# ERN_MainPowerV2.net
KiCad netlist of a schematic drawn in Altium Designer
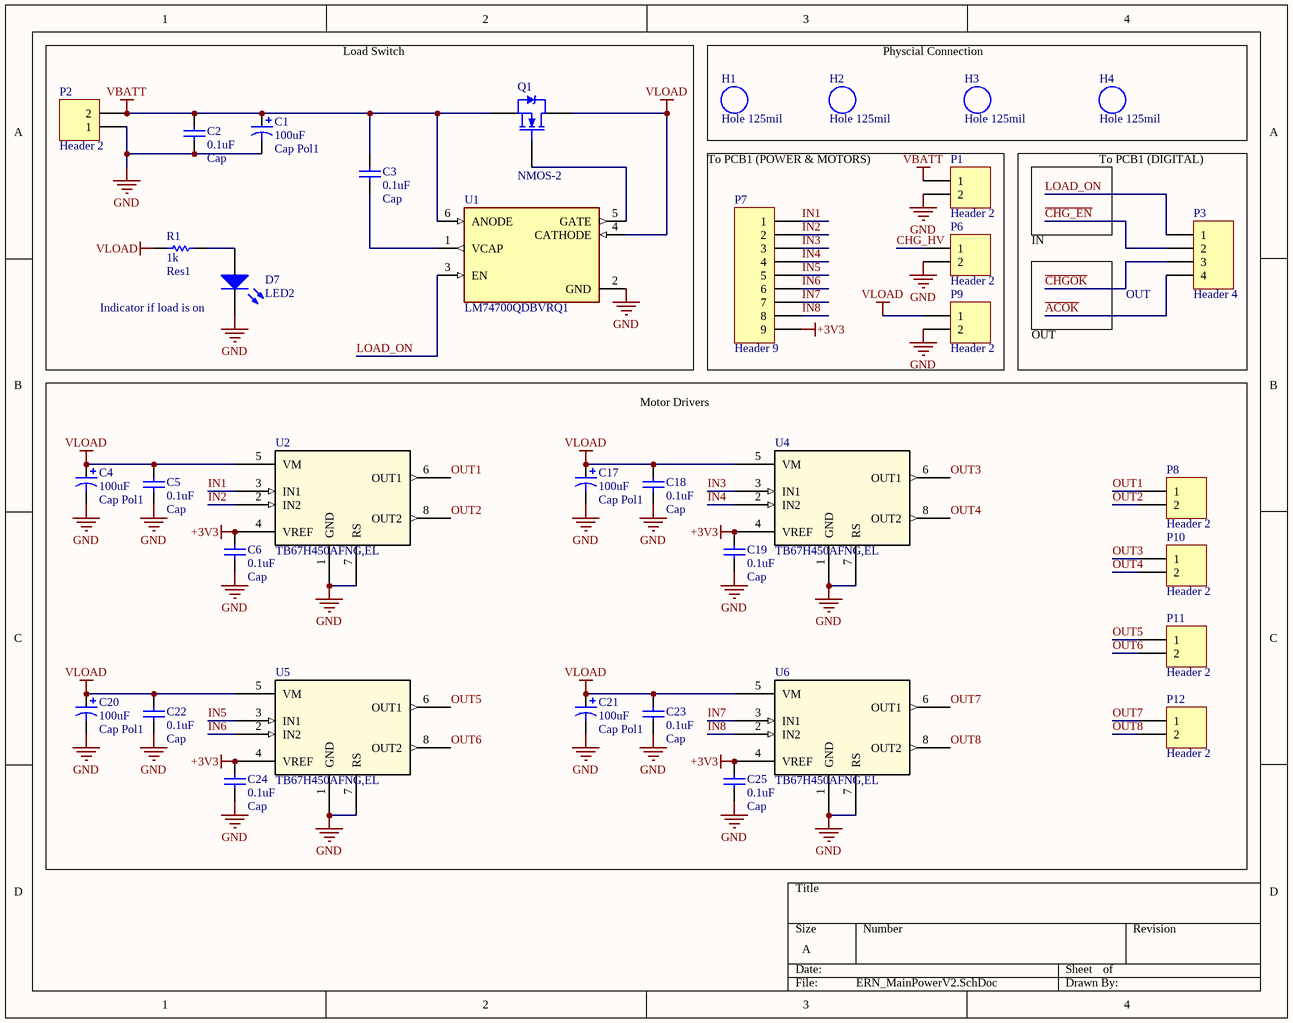
[diagram p0: ERN_MainPowerV2.SchDoc]

(export (version "E")
  (design (tool "Eeschema 10.0.6"))
  (components
    (comp (ref "C1")
      (value "Cap Pol1")
      (footprint "Cap_47uF_100uF")
      (description "Polarized Capacitor (Radial)")
      (fields (field (name "ALTIUM_VALUE") "100uF") (field (name "PUBLISHER") "Altium Limited"))
      (libsource (lib "Miscellaneous Devices") (part "Cap Pol1"))
    )
    (comp (ref "C2")
      (value "Cap")
      (footprint "RAD-0.3")
      (description "Capacitor")
      (fields (field (name "ALTIUM_VALUE") "0.1uF") (field (name "PUBLISHER") "Altium Limited"))
      (libsource (lib "Miscellaneous Devices") (part "Cap"))
    )
    (comp (ref "C3")
      (value "Cap")
      (footprint "C0805")
      (description "Capacitor")
      (fields (field (name "ALTIUM_VALUE") "0.1uF") (field (name "PUBLISHER") "Altium Limited"))
      (libsource (lib "Miscellaneous Devices") (part "Cap"))
    )
    (comp (ref "C4")
      (value "Cap Pol1")
      (footprint "Cap_47uF_100uF")
      (description "Polarized Capacitor (Radial)")
      (fields (field (name "ALTIUM_VALUE") "100uF") (field (name "PUBLISHER") "Altium Limited"))
      (libsource (lib "Miscellaneous Devices") (part "Cap Pol1"))
    )
    (comp (ref "C5")
      (value "Cap")
      (footprint "C0805")
      (description "Capacitor")
      (fields (field (name "ALTIUM_VALUE") "0.1uF") (field (name "PUBLISHER") "Altium Limited"))
      (libsource (lib "Miscellaneous Devices") (part "Cap"))
    )
    (comp (ref "C6")
      (value "Cap")
      (footprint "RAD-0.3")
      (description "Capacitor")
      (fields (field (name "ALTIUM_VALUE") "0.1uF") (field (name "PUBLISHER") "Altium Limited"))
      (libsource (lib "Miscellaneous Devices") (part "Cap"))
    )
    (comp (ref "C17")
      (value "Cap Pol1")
      (footprint "Cap_47uF_100uF")
      (description "Polarized Capacitor (Radial)")
      (fields (field (name "ALTIUM_VALUE") "100uF") (field (name "PUBLISHER") "Altium Limited"))
      (libsource (lib "Miscellaneous Devices") (part "Cap Pol1"))
    )
    (comp (ref "C18")
      (value "Cap")
      (footprint "C0805")
      (description "Capacitor")
      (fields (field (name "ALTIUM_VALUE") "0.1uF") (field (name "PUBLISHER") "Altium Limited"))
      (libsource (lib "Miscellaneous Devices") (part "Cap"))
    )
    (comp (ref "C19")
      (value "Cap")
      (footprint "RAD-0.3")
      (description "Capacitor")
      (fields (field (name "ALTIUM_VALUE") "0.1uF") (field (name "PUBLISHER") "Altium Limited"))
      (libsource (lib "Miscellaneous Devices") (part "Cap"))
    )
    (comp (ref "C20")
      (value "Cap Pol1")
      (footprint "Cap_47uF_100uF")
      (description "Polarized Capacitor (Radial)")
      (fields (field (name "ALTIUM_VALUE") "100uF") (field (name "PUBLISHER") "Altium Limited"))
      (libsource (lib "Miscellaneous Devices") (part "Cap Pol1"))
    )
    (comp (ref "C21")
      (value "Cap Pol1")
      (footprint "Cap_47uF_100uF")
      (description "Polarized Capacitor (Radial)")
      (fields (field (name "ALTIUM_VALUE") "100uF") (field (name "PUBLISHER") "Altium Limited"))
      (libsource (lib "Miscellaneous Devices") (part "Cap Pol1"))
    )
    (comp (ref "C22")
      (value "Cap")
      (footprint "C0805")
      (description "Capacitor")
      (fields (field (name "ALTIUM_VALUE") "0.1uF") (field (name "PUBLISHER") "Altium Limited"))
      (libsource (lib "Miscellaneous Devices") (part "Cap"))
    )
    (comp (ref "C23")
      (value "Cap")
      (footprint "C0805")
      (description "Capacitor")
      (fields (field (name "ALTIUM_VALUE") "0.1uF") (field (name "PUBLISHER") "Altium Limited"))
      (libsource (lib "Miscellaneous Devices") (part "Cap"))
    )
    (comp (ref "C24")
      (value "Cap")
      (footprint "RAD-0.3")
      (description "Capacitor")
      (fields (field (name "ALTIUM_VALUE") "0.1uF") (field (name "PUBLISHER") "Altium Limited"))
      (libsource (lib "Miscellaneous Devices") (part "Cap"))
    )
    (comp (ref "C25")
      (value "Cap")
      (footprint "RAD-0.3")
      (description "Capacitor")
      (fields (field (name "ALTIUM_VALUE") "0.1uF") (field (name "PUBLISHER") "Altium Limited"))
      (libsource (lib "Miscellaneous Devices") (part "Cap"))
    )
    (comp (ref "D7")
      (value "LED2")
      (footprint "led-0")
      (description "Typical RED, GREEN, YELLOW, AMBER GaAs LED")
      (fields (field (name "PUBLISHER") "Altium Limited"))
      (libsource (lib "Miscellaneous Devices") (part "LED2"))
    )
    (comp (ref "H1")
      (value "Hole 125mil")
      (footprint "Hole 125mil")
      (libsource (lib "ECE Lib 22") (part "Hole 125mil"))
    )
    (comp (ref "H2")
      (value "Hole 125mil")
      (footprint "Hole 125mil")
      (libsource (lib "ECE Lib 22") (part "Hole 125mil"))
    )
    (comp (ref "H3")
      (value "Hole 125mil")
      (footprint "Hole 125mil")
      (libsource (lib "ECE Lib 22") (part "Hole 125mil"))
    )
    (comp (ref "H4")
      (value "Hole 125mil")
      (footprint "Hole 125mil")
      (libsource (lib "ECE Lib 22") (part "Hole 125mil"))
    )
    (comp (ref "P1")
      (value "Header 2")
      (footprint "HDR1X2")
      (description "Header, 2-Pin")
      (fields (field (name "PUBLISHER") "Altium Limited"))
      (libsource (lib "Miscellaneous Connectors") (part "Header 2"))
    )
    (comp (ref "P2")
      (value "Header 2")
      (footprint "HDR1X2")
      (description "Header, 2-Pin")
      (fields (field (name "PUBLISHER") "Altium Limited"))
      (libsource (lib "") (part "Header 2_1"))
    )
    (comp (ref "P3")
      (value "Header 4")
      (footprint "HDR1X4")
      (description "Header, 4-Pin")
      (fields (field (name "PUBLISHER") "Altium Limited"))
      (libsource (lib "Miscellaneous Connectors") (part "Header 4"))
    )
    (comp (ref "P6")
      (value "Header 2")
      (footprint "HDR1X2")
      (description "Header, 2-Pin")
      (fields (field (name "PUBLISHER") "Altium Limited"))
      (libsource (lib "Miscellaneous Connectors") (part "Header 2"))
    )
    (comp (ref "P7")
      (value "Header 9")
      (footprint "HDR1X9")
      (description "Header, 9-Pin")
      (fields (field (name "PUBLISHER") "Altium Limited"))
      (libsource (lib "Miscellaneous Connectors") (part "Header 9"))
    )
    (comp (ref "P8")
      (value "Header 2")
      (footprint "HDR1X2")
      (description "Header, 2-Pin")
      (fields (field (name "PUBLISHER") "Altium Limited"))
      (libsource (lib "Miscellaneous Connectors") (part "Header 2"))
    )
    (comp (ref "P9")
      (value "Header 2")
      (footprint "HDR1X2")
      (description "Header, 2-Pin")
      (fields (field (name "PUBLISHER") "Altium Limited"))
      (libsource (lib "Miscellaneous Connectors") (part "Header 2"))
    )
    (comp (ref "P10")
      (value "Header 2")
      (footprint "HDR1X2")
      (description "Header, 2-Pin")
      (fields (field (name "PUBLISHER") "Altium Limited"))
      (libsource (lib "Miscellaneous Connectors") (part "Header 2"))
    )
    (comp (ref "P11")
      (value "Header 2")
      (footprint "HDR1X2")
      (description "Header, 2-Pin")
      (fields (field (name "PUBLISHER") "Altium Limited"))
      (libsource (lib "Miscellaneous Connectors") (part "Header 2"))
    )
    (comp (ref "P12")
      (value "Header 2")
      (footprint "HDR1X2")
      (description "Header, 2-Pin")
      (fields (field (name "PUBLISHER") "Altium Limited"))
      (libsource (lib "Miscellaneous Connectors") (part "Header 2"))
    )
    (comp (ref "Q1")
      (value "NMOS-2")
      (footprint "TO-220AB")
      (description "N-Channel Power MOSFET")
      (fields (field (name "PUBLISHER") "Altium Limited"))
      (libsource (lib "Miscellaneous Devices") (part "NMOS-2"))
    )
    (comp (ref "R1")
      (value "Res1")
      (footprint "AXIAL-0.3")
      (description "Resistor")
      (fields (field (name "ALTIUM_VALUE") "1k") (field (name "PUBLISHER") "Altium Limited"))
      (libsource (lib "Miscellaneous Devices") (part "Res1"))
    )
    (comp (ref "U1")
      (value "LM74700QDBVRQ1")
      (footprint "SOT95P280X145-6N")
      (description "3.2-V to 65-V, 80-uA IQ automotive ideal diode controller")
      (fields (field (name "MF") "Texas Instruments"))
      (libsource (lib "ERN") (part "LM74700QDBVRQ1"))
    )
    (comp (ref "U2")
      (value "TB67H450AFNG,EL")
      (footprint "P-HSOP8-0405-1.27-002_TOS")
      (description "Toshiba Motor Driver IC")
      (fields (field (name "COPYRIGHT") "Copyright (C) 2025 Ultra Librarian. All rights reserved."))
      (libsource (lib "ERN") (part "TB67H450AFNG,EL"))
    )
    (comp (ref "U4")
      (value "TB67H450AFNG,EL")
      (footprint "P-HSOP8-0405-1.27-002_TOS")
      (description "Toshiba Motor Driver IC")
      (fields (field (name "COPYRIGHT") "Copyright (C) 2025 Ultra Librarian. All rights reserved."))
      (libsource (lib "ERN") (part "TB67H450AFNG,EL"))
    )
    (comp (ref "U5")
      (value "TB67H450AFNG,EL")
      (footprint "P-HSOP8-0405-1.27-002_TOS")
      (description "Toshiba Motor Driver IC")
      (fields (field (name "COPYRIGHT") "Copyright (C) 2025 Ultra Librarian. All rights reserved."))
      (libsource (lib "ERN") (part "TB67H450AFNG,EL"))
    )
    (comp (ref "U6")
      (value "TB67H450AFNG,EL")
      (footprint "P-HSOP8-0405-1.27-002_TOS")
      (description "Toshiba Motor Driver IC")
      (fields (field (name "COPYRIGHT") "Copyright (C) 2025 Ultra Librarian. All rights reserved."))
      (libsource (lib "ERN") (part "TB67H450AFNG,EL"))
    )
  )
  (nets
    (net (code "1") (name "+3V3") (class "Default")
      (node (ref "C19") (pin "2") (pinfunction "2_2") (pintype "passive"))
      (node (ref "C24") (pin "2") (pinfunction "2_2") (pintype "passive"))
      (node (ref "C25") (pin "2") (pinfunction "2_2") (pintype "passive"))
      (node (ref "C6") (pin "2") (pinfunction "2_2") (pintype "passive"))
      (node (ref "P7") (pin "9") (pinfunction "9_9") (pintype "passive"))
      (node (ref "U2") (pin "4") (pinfunction "VREF_4") (pintype "passive"))
      (node (ref "U4") (pin "4") (pinfunction "VREF_4") (pintype "passive"))
      (node (ref "U5") (pin "4") (pinfunction "VREF_4") (pintype "passive"))
      (node (ref "U6") (pin "4") (pinfunction "VREF_4") (pintype "passive"))
    )
    (net (code "2") (name "/CHG_HV") (class "Default")
      (node (ref "P6") (pin "1") (pinfunction "1_1") (pintype "passive"))
    )
    (net (code "3") (name "/IN1") (class "Default")
      (node (ref "P7") (pin "1") (pinfunction "1_1") (pintype "passive"))
      (node (ref "U2") (pin "3") (pinfunction "IN1_3") (pintype "input"))
    )
    (net (code "4") (name "/IN2") (class "Default")
      (node (ref "P7") (pin "2") (pinfunction "2_2") (pintype "passive"))
      (node (ref "U2") (pin "2") (pinfunction "IN2_2") (pintype "input"))
    )
    (net (code "5") (name "/IN3") (class "Default")
      (node (ref "P7") (pin "3") (pinfunction "3_3") (pintype "passive"))
      (node (ref "U4") (pin "3") (pinfunction "IN1_3") (pintype "input"))
    )
    (net (code "6") (name "/IN4") (class "Default")
      (node (ref "P7") (pin "4") (pinfunction "4_4") (pintype "passive"))
      (node (ref "U4") (pin "2") (pinfunction "IN2_2") (pintype "input"))
    )
    (net (code "7") (name "/IN5") (class "Default")
      (node (ref "P7") (pin "5") (pinfunction "5_5") (pintype "passive"))
      (node (ref "U5") (pin "3") (pinfunction "IN1_3") (pintype "input"))
    )
    (net (code "8") (name "/IN6") (class "Default")
      (node (ref "P7") (pin "6") (pinfunction "6_6") (pintype "passive"))
      (node (ref "U5") (pin "2") (pinfunction "IN2_2") (pintype "input"))
    )
    (net (code "9") (name "/IN7") (class "Default")
      (node (ref "P7") (pin "7") (pinfunction "7_7") (pintype "passive"))
      (node (ref "U6") (pin "3") (pinfunction "IN1_3") (pintype "input"))
    )
    (net (code "10") (name "/IN8") (class "Default")
      (node (ref "P7") (pin "8") (pinfunction "8_8") (pintype "passive"))
      (node (ref "U6") (pin "2") (pinfunction "IN2_2") (pintype "input"))
    )
    (net (code "11") (name "/LOAD_ON") (class "Default")
      (node (ref "P3") (pin "1") (pinfunction "1_1") (pintype "passive"))
      (node (ref "U1") (pin "3") (pinfunction "EN_3") (pintype "input"))
    )
    (net (code "12") (name "/OUT1") (class "Default")
      (node (ref "P8") (pin "1") (pinfunction "1_1") (pintype "passive"))
      (node (ref "U2") (pin "6") (pinfunction "OUT1_6") (pintype "output"))
    )
    (net (code "13") (name "/OUT2") (class "Default")
      (node (ref "P8") (pin "2") (pinfunction "2_2") (pintype "passive"))
      (node (ref "U2") (pin "8") (pinfunction "OUT2_8") (pintype "output"))
    )
    (net (code "14") (name "/OUT3") (class "Default")
      (node (ref "P10") (pin "1") (pinfunction "1_1") (pintype "passive"))
      (node (ref "U4") (pin "6") (pinfunction "OUT1_6") (pintype "output"))
    )
    (net (code "15") (name "/OUT4") (class "Default")
      (node (ref "P10") (pin "2") (pinfunction "2_2") (pintype "passive"))
      (node (ref "U4") (pin "8") (pinfunction "OUT2_8") (pintype "output"))
    )
    (net (code "16") (name "/OUT5") (class "Default")
      (node (ref "P11") (pin "1") (pinfunction "1_1") (pintype "passive"))
      (node (ref "U5") (pin "6") (pinfunction "OUT1_6") (pintype "output"))
    )
    (net (code "17") (name "/OUT6") (class "Default")
      (node (ref "P11") (pin "2") (pinfunction "2_2") (pintype "passive"))
      (node (ref "U5") (pin "8") (pinfunction "OUT2_8") (pintype "output"))
    )
    (net (code "18") (name "/OUT7") (class "Default")
      (node (ref "P12") (pin "1") (pinfunction "1_1") (pintype "passive"))
      (node (ref "U6") (pin "6") (pinfunction "OUT1_6") (pintype "output"))
    )
    (net (code "19") (name "/OUT8") (class "Default")
      (node (ref "P12") (pin "2") (pinfunction "2_2") (pintype "passive"))
      (node (ref "U6") (pin "8") (pinfunction "OUT2_8") (pintype "output"))
    )
    (net (code "20") (name "/~{ACOK}") (class "Default")
      (node (ref "P3") (pin "4") (pinfunction "4_4") (pintype "passive"))
    )
    (net (code "21") (name "/~{CHGOK}") (class "Default")
      (node (ref "P3") (pin "3") (pinfunction "3_3") (pintype "passive"))
    )
    (net (code "22") (name "/~{CHG_EN}") (class "Default")
      (node (ref "P3") (pin "2") (pinfunction "2_2") (pintype "passive"))
    )
    (net (code "23") (name "GND") (class "Default")
      (node (ref "C1") (pin "2") (pinfunction "2_2") (pintype "passive"))
      (node (ref "C17") (pin "2") (pinfunction "2_2") (pintype "passive"))
      (node (ref "C18") (pin "1") (pinfunction "1_1") (pintype "passive"))
      (node (ref "C19") (pin "1") (pinfunction "1_1") (pintype "passive"))
      (node (ref "C2") (pin "1") (pinfunction "1_1") (pintype "passive"))
      (node (ref "C20") (pin "2") (pinfunction "2_2") (pintype "passive"))
      (node (ref "C21") (pin "2") (pinfunction "2_2") (pintype "passive"))
      (node (ref "C22") (pin "1") (pinfunction "1_1") (pintype "passive"))
      (node (ref "C23") (pin "1") (pinfunction "1_1") (pintype "passive"))
      (node (ref "C24") (pin "1") (pinfunction "1_1") (pintype "passive"))
      (node (ref "C25") (pin "1") (pinfunction "1_1") (pintype "passive"))
      (node (ref "C4") (pin "2") (pinfunction "2_2") (pintype "passive"))
      (node (ref "C5") (pin "1") (pinfunction "1_1") (pintype "passive"))
      (node (ref "C6") (pin "1") (pinfunction "1_1") (pintype "passive"))
      (node (ref "D7") (pin "2") (pinfunction "K_2") (pintype "passive"))
      (node (ref "P1") (pin "2") (pinfunction "2_2") (pintype "passive"))
      (node (ref "P2") (pin "1") (pinfunction "1_1") (pintype "passive"))
      (node (ref "P6") (pin "2") (pinfunction "2_2") (pintype "passive"))
      (node (ref "P9") (pin "2") (pinfunction "2_2") (pintype "passive"))
      (node (ref "U1") (pin "2") (pinfunction "GND_2") (pintype "power_in"))
      (node (ref "U2") (pin "1") (pinfunction "GND_1") (pintype "power_in"))
      (node (ref "U2") (pin "7") (pinfunction "RS_7") (pintype "passive"))
      (node (ref "U4") (pin "1") (pinfunction "GND_1") (pintype "power_in"))
      (node (ref "U4") (pin "7") (pinfunction "RS_7") (pintype "passive"))
      (node (ref "U5") (pin "1") (pinfunction "GND_1") (pintype "power_in"))
      (node (ref "U5") (pin "7") (pinfunction "RS_7") (pintype "passive"))
      (node (ref "U6") (pin "1") (pinfunction "GND_1") (pintype "power_in"))
      (node (ref "U6") (pin "7") (pinfunction "RS_7") (pintype "passive"))
    )
    (net (code "24") (name "Net-(D7-A)") (class "Default")
      (node (ref "D7") (pin "1") (pinfunction "A_1") (pintype "passive"))
      (node (ref "R1") (pin "2") (pinfunction "2_2") (pintype "passive"))
    )
    (net (code "25") (name "Net-(Q1-G)") (class "Default")
      (node (ref "Q1") (pin "1") (pinfunction "G_1") (pintype "passive"))
      (node (ref "U1") (pin "5") (pinfunction "GATE_5") (pintype "output"))
    )
    (net (code "26") (name "Net-(U1-VCAP)") (class "Default")
      (node (ref "C3") (pin "1") (pinfunction "1_1") (pintype "passive"))
      (node (ref "U1") (pin "1") (pinfunction "VCAP_1") (pintype "output"))
    )
    (net (code "27") (name "VBATT") (class "Default")
      (node (ref "C1") (pin "1") (pinfunction "1_1") (pintype "passive"))
      (node (ref "C2") (pin "2") (pinfunction "2_2") (pintype "passive"))
      (node (ref "C3") (pin "2") (pinfunction "2_2") (pintype "passive"))
      (node (ref "P1") (pin "1") (pinfunction "1_1") (pintype "passive"))
      (node (ref "P2") (pin "2") (pinfunction "2_2") (pintype "passive"))
      (node (ref "Q1") (pin "3") (pinfunction "S_3") (pintype "passive"))
      (node (ref "U1") (pin "6") (pinfunction "ANODE_6") (pintype "input"))
    )
    (net (code "28") (name "VLOAD") (class "Default")
      (node (ref "C17") (pin "1") (pinfunction "1_1") (pintype "passive"))
      (node (ref "C18") (pin "2") (pinfunction "2_2") (pintype "passive"))
      (node (ref "C20") (pin "1") (pinfunction "1_1") (pintype "passive"))
      (node (ref "C21") (pin "1") (pinfunction "1_1") (pintype "passive"))
      (node (ref "C22") (pin "2") (pinfunction "2_2") (pintype "passive"))
      (node (ref "C23") (pin "2") (pinfunction "2_2") (pintype "passive"))
      (node (ref "C4") (pin "1") (pinfunction "1_1") (pintype "passive"))
      (node (ref "C5") (pin "2") (pinfunction "2_2") (pintype "passive"))
      (node (ref "P9") (pin "1") (pinfunction "1_1") (pintype "passive"))
      (node (ref "Q1") (pin "2") (pinfunction "D_2") (pintype "passive"))
      (node (ref "R1") (pin "1") (pinfunction "1_1") (pintype "passive"))
      (node (ref "U1") (pin "4") (pinfunction "CATHODE_4") (pintype "input"))
      (node (ref "U2") (pin "5") (pinfunction "VM_5") (pintype "power_in"))
      (node (ref "U4") (pin "5") (pinfunction "VM_5") (pintype "power_in"))
      (node (ref "U5") (pin "5") (pinfunction "VM_5") (pintype "power_in"))
      (node (ref "U6") (pin "5") (pinfunction "VM_5") (pintype "power_in"))
    )
  )
)
